# DC_MotorDriver.net
KiCad netlist of a schematic drawn in Altium Designer
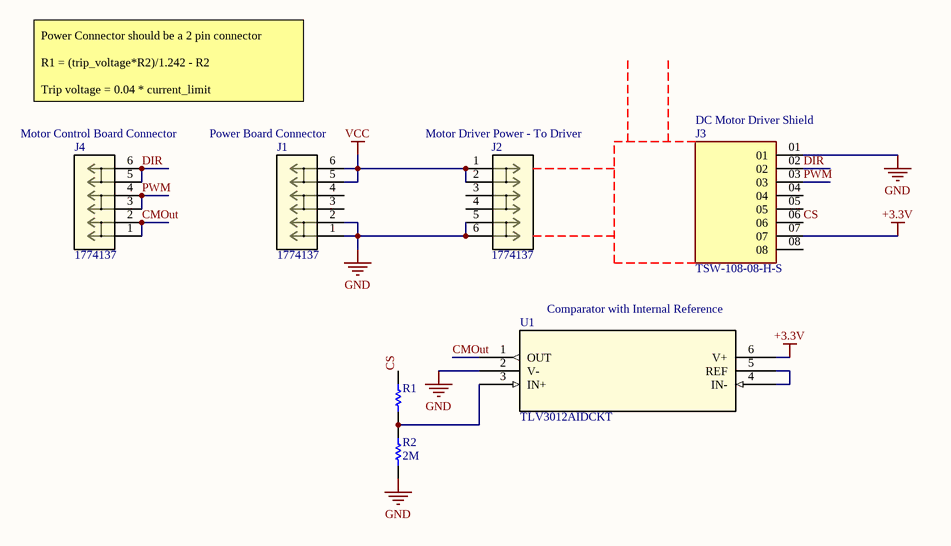
[diagram p0: DC_MotorDriver.SchDoc]

(export (version "E")
  (design (tool "Eeschema 10.0.6"))
  (components
    (comp (ref "J1")
      (value "1774137")
      (footprint "CONN_1774137")
      (description "No Description Available")
      (fields (field (name "COPYRIGHT") "Copyright (C) 2022 Ultra Librarian. All rights reserved."))
      (libsource (lib "1774137") (part "1774137"))
    )
    (comp (ref "J2")
      (value "1774137")
      (footprint "CONN_1774137")
      (description "No Description Available")
      (fields (field (name "COPYRIGHT") "Copyright (C) 2022 Ultra Librarian. All rights reserved."))
      (libsource (lib "") (part "1774137_1"))
    )
    (comp (ref "J3")
      (value "TSW-108-08-H-S")
      (footprint "SAMTEC_TSW-108-08-H-S")
      (libsource (lib "TSW-108-08-H-S") (part "TSW-108-08-H-S"))
    )
    (comp (ref "J4")
      (value "1774137")
      (footprint "CONN_1774137")
      (description "No Description Available")
      (fields (field (name "COPYRIGHT") "Copyright (C) 2022 Ultra Librarian. All rights reserved."))
      (libsource (lib "1774137") (part "1774137"))
    )
    (comp (ref "R1")
      (value "~")
      (footprint "RES_0603")
      (description "RES SMD 249 OHM 1% 1/10W 0603")
      (fields
        (field (name "MANUFACTURER") "Panasonic Electronic Components")
        (field (name "MANUFACTURER PART NUMBER") "ERJ-3EKF2490V")
      )
      (libsource (lib "Resistors") (part "249_1%_0603"))
    )
    (comp (ref "R2")
      (value "2M")
      (footprint "RES_0603")
      (description "RES SMD 249 OHM 1% 1/10W 0603")
      (fields
        (field (name "MANUFACTURER") "Panasonic Electronic Components")
        (field (name "MANUFACTURER PART NUMBER") "ERJ-3EKF2490V")
      )
      (libsource (lib "Resistors") (part "249_1%_0603"))
    )
    (comp (ref "U1")
      (value "TLV3012AIDCKT")
      (footprint "DCK6")
      (description "No Description Available")
      (fields (field (name "COPYRIGHT") "Copyright (C) 2022 Ultra Librarian. All rights reserved."))
      (libsource (lib "TLV3012AIDCKT") (part "TLV3012AIDCKT"))
    )
  )
  (nets
    (net (code "1") (name "+3.3V") (class "Default")
      (node (ref "J3") (pin "07") (pinfunction "07_07") (pintype "passive"))
      (node (ref "U1") (pin "6") (pinfunction "V+_6") (pintype "power_in"))
    )
    (net (code "2") (name "/CMOut") (class "Default")
      (node (ref "J4") (pin "1") (pinfunction "1_1") (pintype "passive"))
      (node (ref "J4") (pin "2") (pinfunction "2_2") (pintype "passive"))
      (node (ref "U1") (pin "1") (pinfunction "OUT_1") (pintype "output"))
    )
    (net (code "3") (name "/CS") (class "Default")
      (node (ref "J3") (pin "06") (pinfunction "06_06") (pintype "passive"))
      (node (ref "R1") (pin "2") (pinfunction "2_2") (pintype "passive"))
    )
    (net (code "4") (name "/DIR") (class "Default")
      (node (ref "J3") (pin "02") (pinfunction "02_02") (pintype "passive"))
      (node (ref "J4") (pin "5") (pinfunction "5_5") (pintype "passive"))
      (node (ref "J4") (pin "6") (pinfunction "6_6") (pintype "passive"))
    )
    (net (code "5") (name "/PWM") (class "Default")
      (node (ref "J3") (pin "03") (pinfunction "03_03") (pintype "passive"))
      (node (ref "J4") (pin "3") (pinfunction "3_3") (pintype "passive"))
      (node (ref "J4") (pin "4") (pinfunction "4_4") (pintype "passive"))
    )
    (net (code "6") (name "GND") (class "Default")
      (node (ref "J1") (pin "1") (pinfunction "1_1") (pintype "passive"))
      (node (ref "J1") (pin "2") (pinfunction "2_2") (pintype "passive"))
      (node (ref "J2") (pin "5") (pinfunction "5_5") (pintype "passive"))
      (node (ref "J2") (pin "6") (pinfunction "6_6") (pintype "passive"))
      (node (ref "J3") (pin "01") (pinfunction "01_01") (pintype "passive"))
      (node (ref "R2") (pin "1") (pinfunction "1_1") (pintype "passive"))
      (node (ref "U1") (pin "2") (pinfunction "V-_2") (pintype "power_in"))
    )
    (net (code "7") (name "Net-(U1-IN+)") (class "Default")
      (node (ref "R1") (pin "1") (pinfunction "1_1") (pintype "passive"))
      (node (ref "R2") (pin "2") (pinfunction "2_2") (pintype "passive"))
      (node (ref "U1") (pin "3") (pinfunction "IN+_3") (pintype "input"))
    )
    (net (code "8") (name "Net-(U1-IN-)") (class "Default")
      (node (ref "U1") (pin "4") (pinfunction "IN-_4") (pintype "input"))
      (node (ref "U1") (pin "5") (pinfunction "REF_5") (pintype "power_in"))
    )
    (net (code "9") (name "VCC") (class "Default")
      (node (ref "J1") (pin "5") (pinfunction "5_5") (pintype "passive"))
      (node (ref "J1") (pin "6") (pinfunction "6_6") (pintype "passive"))
      (node (ref "J2") (pin "1") (pinfunction "1_1") (pintype "passive"))
      (node (ref "J2") (pin "2") (pinfunction "2_2") (pintype "passive"))
    )
    (net (code "10") (name "unconnected-(J1-Pad3)") (class "Default")
      (node (ref "J1") (pin "3") (pinfunction "3_3") (pintype "passive"))
    )
    (net (code "11") (name "unconnected-(J1-Pad4)") (class "Default")
      (node (ref "J1") (pin "4") (pinfunction "4_4") (pintype "passive"))
    )
    (net (code "12") (name "unconnected-(J2-Pad3)") (class "Default")
      (node (ref "J2") (pin "3") (pinfunction "3_3") (pintype "passive"))
    )
    (net (code "13") (name "unconnected-(J2-Pad4)") (class "Default")
      (node (ref "J2") (pin "4") (pinfunction "4_4") (pintype "passive"))
    )
    (net (code "14") (name "unconnected-(J3-Pad04)") (class "Default")
      (node (ref "J3") (pin "04") (pinfunction "04_04") (pintype "passive"))
    )
    (net (code "15") (name "unconnected-(J3-Pad05)") (class "Default")
      (node (ref "J3") (pin "05") (pinfunction "05_05") (pintype "passive"))
    )
    (net (code "16") (name "unconnected-(J3-Pad08)") (class "Default")
      (node (ref "J3") (pin "08") (pinfunction "08_08") (pintype "passive"))
    )
  )
)
